# Extern_Kernal_REX9628.net
KiCad netlist of a schematic drawn in EAGLE
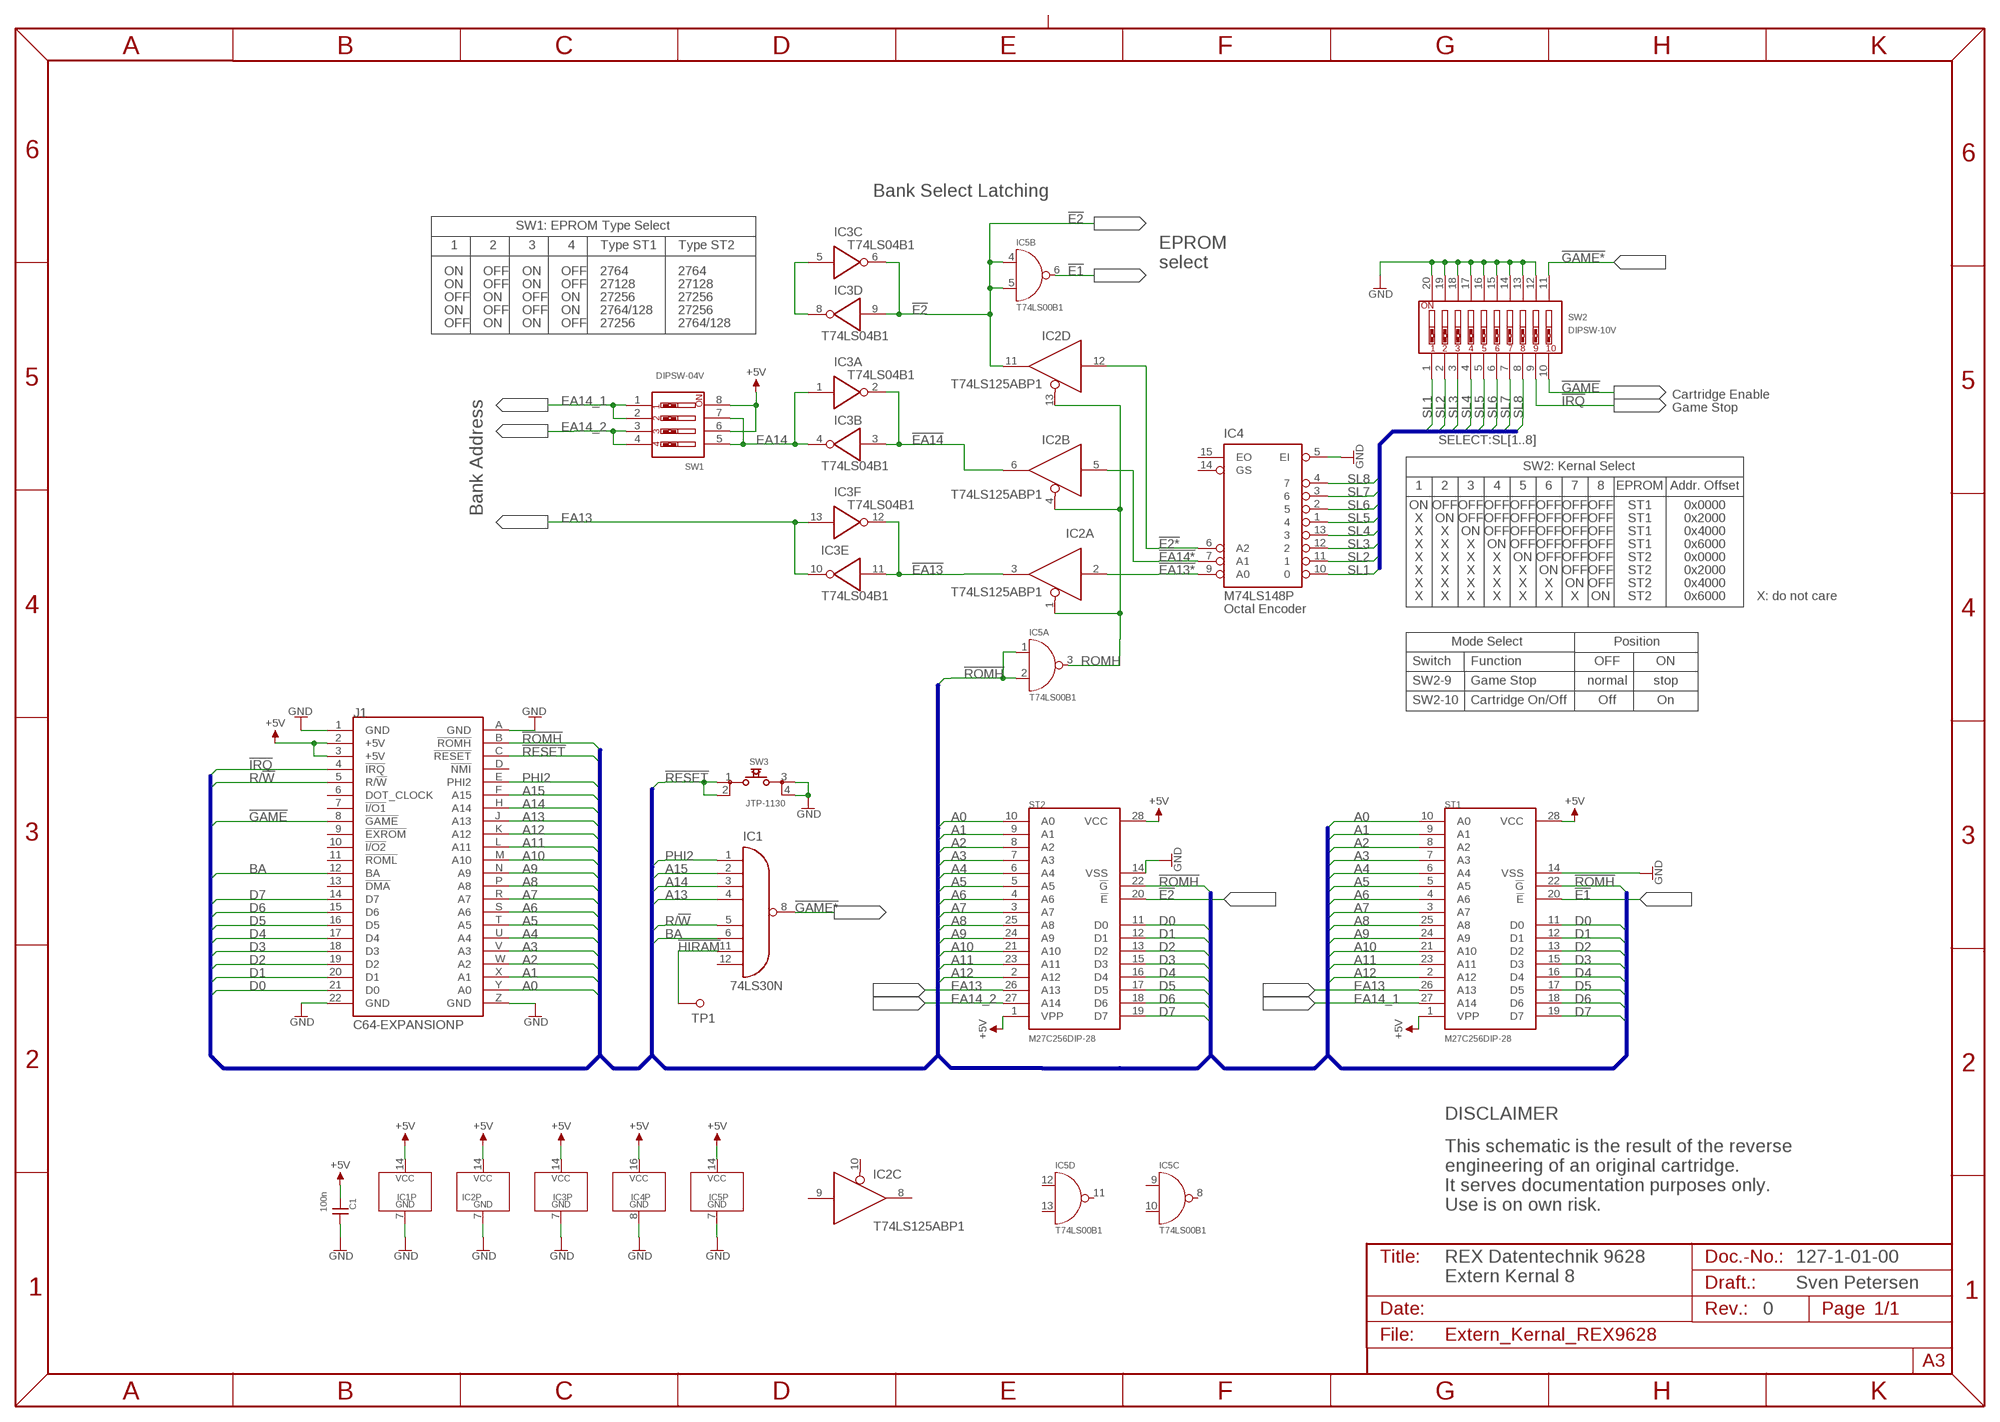
[diagram p0: schematic, sheet 1]

(export (version "E")
  (design (tool "Eeschema 10.0.6"))
  (components
    (comp (ref "C1")
      (value "100n")
      (footprint "eagle-import:C-2,5")
      (libsource (lib "eagle-import") (part "CAP01"))
    )
    (comp (ref "IC1")
      (value "74LS30N")
      (footprint "eagle-import:DIL-14")
      (libsource (lib "eagle-import") (part "7430DIP"))
    )
    (comp (ref "IC2")
      (value "T74LS125ABP1")
      (footprint "eagle-import:DIL-14")
      (libsource (lib "eagle-import") (part "74125DIP"))
    )
    (comp (ref "IC3")
      (value "T74LS04B1")
      (footprint "eagle-import:DIL-14")
      (libsource (lib "eagle-import") (part "7404DIL"))
    )
    (comp (ref "IC4")
      (value "M74LS148P")
      (footprint "eagle-import:DIL-16")
      (libsource (lib "eagle-import") (part "74148DIL"))
    )
    (comp (ref "IC5")
      (value "T74LS00B1")
      (footprint "eagle-import:DIL-14")
      (libsource (lib "eagle-import") (part "7400DIP"))
    )
    (comp (ref "J1")
      (value "C64-EXPANSIONP")
      (footprint "eagle-import:EXPPORT")
      (libsource (lib "eagle-import") (part "C64-EXPANSIONP"))
    )
    (comp (ref "ST1")
      (value "M27C256DIP-28")
      (footprint "eagle-import:DIL28-6")
      (libsource (lib "eagle-import") (part "M27C256DIP-28"))
    )
    (comp (ref "ST2")
      (value "M27C256DIP-28")
      (footprint "eagle-import:DIL28-6")
      (libsource (lib "eagle-import") (part "M27C256DIP-28"))
    )
    (comp (ref "SW1")
      (value "DIPSW-04V")
      (footprint "eagle-import:DIPSW-04V")
      (libsource (lib "eagle-import") (part "DIPSW-04V"))
    )
    (comp (ref "SW2")
      (value "DIPSW-10V")
      (footprint "eagle-import:DIPSW-10V")
      (libsource (lib "eagle-import") (part "DIPSW-10V"))
    )
    (comp (ref "SW3")
      (value "JTP-1130")
      (footprint "eagle-import:JTP-1130")
      (libsource (lib "eagle-import") (part "JTP-1130"))
    )
    (comp (ref "TP1")
      (value "1,3/2,0")
      (footprint "eagle-import:1,3_2,0")
      (libsource (lib "eagle-import") (part "1,3/2,0"))
    )
  )
  (nets
    (net (code "9") (name "+5V") (class "Default")
      (node (ref "C1") (pin "1") (pinfunction "1_1") (pintype "passive"))
      (node (ref "IC1") (pin "14") (pinfunction "VCC_14") (pintype "bidirectional"))
      (node (ref "IC2") (pin "14") (pinfunction "VCC_14") (pintype "bidirectional"))
      (node (ref "IC3") (pin "14") (pinfunction "VCC_14") (pintype "bidirectional"))
      (node (ref "IC4") (pin "16") (pinfunction "VCC_16") (pintype "bidirectional"))
      (node (ref "IC5") (pin "14") (pinfunction "VCC_14") (pintype "bidirectional"))
      (node (ref "J1") (pin "2") (pinfunction "+5V_2") (pintype "power_in"))
      (node (ref "J1") (pin "3") (pinfunction "+5V_3") (pintype "power_in"))
      (node (ref "ST1") (pin "1") (pinfunction "VPP_1") (pintype "input"))
      (node (ref "ST1") (pin "28") (pinfunction "VCC_28") (pintype "power_in"))
      (node (ref "ST2") (pin "1") (pinfunction "VPP_1") (pintype "input"))
      (node (ref "ST2") (pin "28") (pinfunction "VCC_28") (pintype "power_in"))
      (node (ref "SW1") (pin "6") (pinfunction "6_6") (pintype "passive"))
      (node (ref "SW1") (pin "8") (pinfunction "8_8") (pintype "passive"))
    )
    (net (code "10") (name "/A0") (class "Default")
      (node (ref "J1") (pin "Y") (pinfunction "A0_Y") (pintype "bidirectional"))
      (node (ref "ST1") (pin "10") (pinfunction "A0_10") (pintype "input"))
      (node (ref "ST2") (pin "10") (pinfunction "A0_10") (pintype "input"))
    )
    (net (code "11") (name "/A1") (class "Default")
      (node (ref "J1") (pin "X") (pinfunction "A1_X") (pintype "bidirectional"))
      (node (ref "ST1") (pin "9") (pinfunction "A1_9") (pintype "input"))
      (node (ref "ST2") (pin "9") (pinfunction "A1_9") (pintype "input"))
    )
    (net (code "12") (name "/A2") (class "Default")
      (node (ref "J1") (pin "W") (pinfunction "A2_W") (pintype "bidirectional"))
      (node (ref "ST1") (pin "8") (pinfunction "A2_8") (pintype "input"))
      (node (ref "ST2") (pin "8") (pinfunction "A2_8") (pintype "input"))
    )
    (net (code "13") (name "/A3") (class "Default")
      (node (ref "J1") (pin "V") (pinfunction "A3_V") (pintype "bidirectional"))
      (node (ref "ST1") (pin "7") (pinfunction "A3_7") (pintype "input"))
      (node (ref "ST2") (pin "7") (pinfunction "A3_7") (pintype "input"))
    )
    (net (code "14") (name "/A4") (class "Default")
      (node (ref "J1") (pin "U") (pinfunction "A4_U") (pintype "bidirectional"))
      (node (ref "ST1") (pin "6") (pinfunction "A4_6") (pintype "input"))
      (node (ref "ST2") (pin "6") (pinfunction "A4_6") (pintype "input"))
    )
    (net (code "15") (name "/A5") (class "Default")
      (node (ref "J1") (pin "T") (pinfunction "A5_T") (pintype "bidirectional"))
      (node (ref "ST1") (pin "5") (pinfunction "A5_5") (pintype "input"))
      (node (ref "ST2") (pin "5") (pinfunction "A5_5") (pintype "input"))
    )
    (net (code "16") (name "/A6") (class "Default")
      (node (ref "J1") (pin "S") (pinfunction "A6_S") (pintype "bidirectional"))
      (node (ref "ST1") (pin "4") (pinfunction "A6_4") (pintype "input"))
      (node (ref "ST2") (pin "4") (pinfunction "A6_4") (pintype "input"))
    )
    (net (code "17") (name "/A7") (class "Default")
      (node (ref "J1") (pin "R") (pinfunction "A7_R") (pintype "bidirectional"))
      (node (ref "ST1") (pin "3") (pinfunction "A7_3") (pintype "input"))
      (node (ref "ST2") (pin "3") (pinfunction "A7_3") (pintype "input"))
    )
    (net (code "18") (name "/A8") (class "Default")
      (node (ref "J1") (pin "P") (pinfunction "A8_P") (pintype "bidirectional"))
      (node (ref "ST1") (pin "25") (pinfunction "A8_25") (pintype "input"))
      (node (ref "ST2") (pin "25") (pinfunction "A8_25") (pintype "input"))
    )
    (net (code "19") (name "/A9") (class "Default")
      (node (ref "J1") (pin "N") (pinfunction "A9_N") (pintype "bidirectional"))
      (node (ref "ST1") (pin "24") (pinfunction "A9_24") (pintype "input"))
      (node (ref "ST2") (pin "24") (pinfunction "A9_24") (pintype "input"))
    )
    (net (code "20") (name "/A10") (class "Default")
      (node (ref "J1") (pin "M") (pinfunction "A10_M") (pintype "bidirectional"))
      (node (ref "ST1") (pin "21") (pinfunction "A10_21") (pintype "input"))
      (node (ref "ST2") (pin "21") (pinfunction "A10_21") (pintype "input"))
    )
    (net (code "21") (name "/A11") (class "Default")
      (node (ref "J1") (pin "L") (pinfunction "A11_L") (pintype "bidirectional"))
      (node (ref "ST1") (pin "23") (pinfunction "A11_23") (pintype "input"))
      (node (ref "ST2") (pin "23") (pinfunction "A11_23") (pintype "input"))
    )
    (net (code "22") (name "/A12") (class "Default")
      (node (ref "J1") (pin "K") (pinfunction "A12_K") (pintype "bidirectional"))
      (node (ref "ST1") (pin "2") (pinfunction "A12_2") (pintype "input"))
      (node (ref "ST2") (pin "2") (pinfunction "A12_2") (pintype "input"))
    )
    (net (code "23") (name "/A13") (class "Default")
      (node (ref "IC1") (pin "4") (pinfunction "I3_4") (pintype "input"))
      (node (ref "J1") (pin "J") (pinfunction "A13_J") (pintype "bidirectional"))
    )
    (net (code "24") (name "/A14") (class "Default")
      (node (ref "IC1") (pin "3") (pinfunction "I2_3") (pintype "input"))
      (node (ref "J1") (pin "H") (pinfunction "A14_H") (pintype "bidirectional"))
    )
    (net (code "25") (name "/A15") (class "Default")
      (node (ref "IC1") (pin "2") (pinfunction "I1_2") (pintype "input"))
      (node (ref "J1") (pin "F") (pinfunction "A15_F") (pintype "bidirectional"))
    )
    (net (code "26") (name "/BA") (class "Default")
      (node (ref "IC1") (pin "6") (pinfunction "I5_6") (pintype "input"))
      (node (ref "J1") (pin "12") (pinfunction "BA_12") (pintype "output"))
    )
    (net (code "27") (name "/D0") (class "Default")
      (node (ref "J1") (pin "21") (pinfunction "D0_21") (pintype "bidirectional"))
      (node (ref "ST1") (pin "11") (pinfunction "D0_11") (pintype "bidirectional"))
      (node (ref "ST2") (pin "11") (pinfunction "D0_11") (pintype "bidirectional"))
    )
    (net (code "28") (name "/D1") (class "Default")
      (node (ref "J1") (pin "20") (pinfunction "D1_20") (pintype "bidirectional"))
      (node (ref "ST1") (pin "12") (pinfunction "D1_12") (pintype "bidirectional"))
      (node (ref "ST2") (pin "12") (pinfunction "D1_12") (pintype "bidirectional"))
    )
    (net (code "29") (name "/D2") (class "Default")
      (node (ref "J1") (pin "19") (pinfunction "D2_19") (pintype "bidirectional"))
      (node (ref "ST1") (pin "13") (pinfunction "D2_13") (pintype "bidirectional"))
      (node (ref "ST2") (pin "13") (pinfunction "D2_13") (pintype "bidirectional"))
    )
    (net (code "30") (name "/D3") (class "Default")
      (node (ref "J1") (pin "18") (pinfunction "D3_18") (pintype "bidirectional"))
      (node (ref "ST1") (pin "15") (pinfunction "D3_15") (pintype "bidirectional"))
      (node (ref "ST2") (pin "15") (pinfunction "D3_15") (pintype "bidirectional"))
    )
    (net (code "31") (name "/D4") (class "Default")
      (node (ref "J1") (pin "17") (pinfunction "D4_17") (pintype "bidirectional"))
      (node (ref "ST1") (pin "16") (pinfunction "D4_16") (pintype "bidirectional"))
      (node (ref "ST2") (pin "16") (pinfunction "D4_16") (pintype "bidirectional"))
    )
    (net (code "32") (name "/D5") (class "Default")
      (node (ref "J1") (pin "16") (pinfunction "D5_16") (pintype "bidirectional"))
      (node (ref "ST1") (pin "17") (pinfunction "D5_17") (pintype "bidirectional"))
      (node (ref "ST2") (pin "17") (pinfunction "D5_17") (pintype "bidirectional"))
    )
    (net (code "33") (name "/D6") (class "Default")
      (node (ref "J1") (pin "15") (pinfunction "D6_15") (pintype "bidirectional"))
      (node (ref "ST1") (pin "18") (pinfunction "D6_18") (pintype "bidirectional"))
      (node (ref "ST2") (pin "18") (pinfunction "D6_18") (pintype "bidirectional"))
    )
    (net (code "34") (name "/D7") (class "Default")
      (node (ref "J1") (pin "14") (pinfunction "D7_14") (pintype "bidirectional"))
      (node (ref "ST1") (pin "19") (pinfunction "D7_19") (pintype "bidirectional"))
      (node (ref "ST2") (pin "19") (pinfunction "D7_19") (pintype "bidirectional"))
    )
    (net (code "35") (name "/EA13") (class "Default")
      (node (ref "IC3") (pin "10") (pinfunction "O_10") (pintype "output"))
      (node (ref "IC3") (pin "13") (pinfunction "I_13") (pintype "input"))
      (node (ref "ST1") (pin "26") (pinfunction "A13_26") (pintype "input"))
      (node (ref "ST2") (pin "26") (pinfunction "A13_26") (pintype "input"))
    )
    (net (code "36") (name "/EA14") (class "Default")
      (node (ref "IC3") (pin "1") (pinfunction "I_1") (pintype "input"))
      (node (ref "IC3") (pin "4") (pinfunction "O_4") (pintype "output"))
      (node (ref "SW1") (pin "5") (pinfunction "5_5") (pintype "passive"))
      (node (ref "SW1") (pin "7") (pinfunction "7_7") (pintype "passive"))
    )
    (net (code "37") (name "/EA14_1") (class "Default")
      (node (ref "ST1") (pin "27") (pinfunction "A14_27") (pintype "input"))
      (node (ref "SW1") (pin "1") (pinfunction "1_1") (pintype "passive"))
      (node (ref "SW1") (pin "2") (pinfunction "2_2") (pintype "passive"))
    )
    (net (code "38") (name "/EA14_2") (class "Default")
      (node (ref "ST2") (pin "27") (pinfunction "A14_27") (pintype "input"))
      (node (ref "SW1") (pin "3") (pinfunction "3_3") (pintype "passive"))
      (node (ref "SW1") (pin "4") (pinfunction "4_4") (pintype "passive"))
    )
    (net (code "39") (name "/PHI2") (class "Default")
      (node (ref "IC1") (pin "1") (pinfunction "I0_1") (pintype "input"))
      (node (ref "J1") (pin "E") (pinfunction "PHI2_E") (pintype "output"))
    )
    (net (code "40") (name "/ROMH") (class "Default")
      (node (ref "IC2") (pin "1") (pinfunction "OE_1") (pintype "input"))
      (node (ref "IC2") (pin "13") (pinfunction "OE_13") (pintype "input"))
      (node (ref "IC2") (pin "4") (pinfunction "OE_4") (pintype "input"))
      (node (ref "IC5") (pin "3") (pinfunction "O_3") (pintype "output"))
    )
    (net (code "41") (name "/R{slash}~{W}") (class "Default")
      (node (ref "IC1") (pin "5") (pinfunction "I4_5") (pintype "input"))
      (node (ref "J1") (pin "5") (pinfunction "R/~{W}_5") (pintype "output"))
    )
    (net (code "43") (name "/SL1") (class "Default")
      (node (ref "IC4") (pin "10") (pinfunction "0_10") (pintype "input"))
      (node (ref "SW2") (pin "1") (pinfunction "1_1") (pintype "passive"))
    )
    (net (code "44") (name "/SL2") (class "Default")
      (node (ref "IC4") (pin "11") (pinfunction "1_11") (pintype "input"))
      (node (ref "SW2") (pin "2") (pinfunction "2_2") (pintype "passive"))
    )
    (net (code "45") (name "/SL3") (class "Default")
      (node (ref "IC4") (pin "12") (pinfunction "2_12") (pintype "input"))
      (node (ref "SW2") (pin "3") (pinfunction "3_3") (pintype "passive"))
    )
    (net (code "46") (name "/SL4") (class "Default")
      (node (ref "IC4") (pin "13") (pinfunction "3_13") (pintype "input"))
      (node (ref "SW2") (pin "4") (pinfunction "4_4") (pintype "passive"))
    )
    (net (code "47") (name "/SL5") (class "Default")
      (node (ref "IC4") (pin "1") (pinfunction "4_1") (pintype "input"))
      (node (ref "SW2") (pin "5") (pinfunction "5_5") (pintype "passive"))
    )
    (net (code "48") (name "/SL6") (class "Default")
      (node (ref "IC4") (pin "2") (pinfunction "5_2") (pintype "input"))
      (node (ref "SW2") (pin "6") (pinfunction "6_6") (pintype "passive"))
    )
    (net (code "49") (name "/SL7") (class "Default")
      (node (ref "IC4") (pin "3") (pinfunction "6_3") (pintype "input"))
      (node (ref "SW2") (pin "7") (pinfunction "7_7") (pintype "passive"))
    )
    (net (code "50") (name "/SL8") (class "Default")
      (node (ref "IC4") (pin "4") (pinfunction "7_4") (pintype "input"))
      (node (ref "SW2") (pin "8") (pinfunction "8_8") (pintype "passive"))
    )
    (net (code "51") (name "/~{E1}") (class "Default")
      (node (ref "IC5") (pin "6") (pinfunction "O_6") (pintype "output"))
      (node (ref "ST1") (pin "20") (pinfunction "~{E}_20") (pintype "input"))
    )
    (net (code "52") (name "/~{E2*}") (class "Default")
      (node (ref "IC2") (pin "12") (pinfunction "I_12") (pintype "input"))
      (node (ref "IC4") (pin "6") (pinfunction "A2_6") (pintype "output"))
    )
    (net (code "53") (name "/~{E2}") (class "Default")
      (node (ref "IC2") (pin "11") (pinfunction "O_11") (pintype "tri_state"))
      (node (ref "IC3") (pin "6") (pinfunction "O_6") (pintype "output"))
      (node (ref "IC3") (pin "9") (pinfunction "I_9") (pintype "input"))
      (node (ref "IC5") (pin "4") (pinfunction "I0_4") (pintype "input"))
      (node (ref "IC5") (pin "5") (pinfunction "I1_5") (pintype "input"))
      (node (ref "ST2") (pin "20") (pinfunction "~{E}_20") (pintype "input"))
    )
    (net (code "54") (name "/~{EA13*}") (class "Default")
      (node (ref "IC2") (pin "2") (pinfunction "I_2") (pintype "input"))
      (node (ref "IC4") (pin "9") (pinfunction "A0_9") (pintype "output"))
    )
    (net (code "55") (name "/~{EA13}") (class "Default")
      (node (ref "IC2") (pin "3") (pinfunction "O_3") (pintype "tri_state"))
      (node (ref "IC3") (pin "11") (pinfunction "I_11") (pintype "input"))
      (node (ref "IC3") (pin "12") (pinfunction "O_12") (pintype "output"))
    )
    (net (code "56") (name "/~{EA14*}") (class "Default")
      (node (ref "IC2") (pin "5") (pinfunction "I_5") (pintype "input"))
      (node (ref "IC4") (pin "7") (pinfunction "A1_7") (pintype "output"))
    )
    (net (code "57") (name "/~{EA14}") (class "Default")
      (node (ref "IC2") (pin "6") (pinfunction "O_6") (pintype "tri_state"))
      (node (ref "IC3") (pin "2") (pinfunction "O_2") (pintype "output"))
      (node (ref "IC3") (pin "3") (pinfunction "I_3") (pintype "input"))
    )
    (net (code "58") (name "/~{GAME*}") (class "Default")
      (node (ref "IC1") (pin "8") (pinfunction "O_8") (pintype "output"))
      (node (ref "SW2") (pin "11") (pinfunction "11_11") (pintype "passive"))
    )
    (net (code "59") (name "/~{GAME}") (class "Default")
      (node (ref "J1") (pin "8") (pinfunction "~{GAME}_8") (pintype "input"))
      (node (ref "SW2") (pin "10") (pinfunction "10_10") (pintype "passive"))
    )
    (net (code "60") (name "/~{HIRAM}") (class "Default")
      (node (ref "IC1") (pin "11") (pinfunction "I6_11") (pintype "input"))
      (node (ref "TP1") (pin "1") (pinfunction "1_1") (pintype "passive"))
    )
    (net (code "61") (name "/~{IRQ}") (class "Default")
      (node (ref "J1") (pin "4") (pinfunction "~{IRQ}_4") (pintype "input"))
      (node (ref "SW2") (pin "9") (pinfunction "9_9") (pintype "passive"))
    )
    (net (code "62") (name "/~{RESET}") (class "Default")
      (node (ref "J1") (pin "C") (pinfunction "~{RESET}_C") (pintype "open_collector"))
      (node (ref "SW3") (pin "1") (pinfunction "1_1") (pintype "passive"))
      (node (ref "SW3") (pin "2") (pinfunction "2_2") (pintype "passive"))
    )
    (net (code "63") (name "/~{ROMH}") (class "Default")
      (node (ref "IC5") (pin "1") (pinfunction "I0_1") (pintype "input"))
      (node (ref "IC5") (pin "2") (pinfunction "I1_2") (pintype "input"))
      (node (ref "J1") (pin "B") (pinfunction "~{ROMH}_B") (pintype "output"))
      (node (ref "ST1") (pin "22") (pinfunction "~{G}_22") (pintype "input"))
      (node (ref "ST2") (pin "22") (pinfunction "~{G}_22") (pintype "input"))
    )
    (net (code "64") (name "GND") (class "Default")
      (node (ref "C1") (pin "2") (pinfunction "2_2") (pintype "passive"))
      (node (ref "IC1") (pin "7") (pinfunction "GND_7") (pintype "bidirectional"))
      (node (ref "IC2") (pin "7") (pinfunction "GND_7") (pintype "bidirectional"))
      (node (ref "IC3") (pin "7") (pinfunction "GND_7") (pintype "bidirectional"))
      (node (ref "IC4") (pin "5") (pinfunction "EI_5") (pintype "input"))
      (node (ref "IC4") (pin "8") (pinfunction "GND_8") (pintype "bidirectional"))
      (node (ref "IC5") (pin "7") (pinfunction "GND_7") (pintype "bidirectional"))
      (node (ref "J1") (pin "1") (pinfunction "GND_1") (pintype "power_in"))
      (node (ref "J1") (pin "22") (pinfunction "GND_22") (pintype "power_in"))
      (node (ref "J1") (pin "A") (pinfunction "GND_A") (pintype "power_in"))
      (node (ref "J1") (pin "Z") (pinfunction "GND_Z") (pintype "power_in"))
      (node (ref "ST1") (pin "14") (pinfunction "VSS_14") (pintype "power_in"))
      (node (ref "ST2") (pin "14") (pinfunction "VSS_14") (pintype "power_in"))
      (node (ref "SW2") (pin "12") (pinfunction "12_12") (pintype "passive"))
      (node (ref "SW2") (pin "13") (pinfunction "13_13") (pintype "passive"))
      (node (ref "SW2") (pin "14") (pinfunction "14_14") (pintype "passive"))
      (node (ref "SW2") (pin "15") (pinfunction "15_15") (pintype "passive"))
      (node (ref "SW2") (pin "16") (pinfunction "16_16") (pintype "passive"))
      (node (ref "SW2") (pin "17") (pinfunction "17_17") (pintype "passive"))
      (node (ref "SW2") (pin "18") (pinfunction "18_18") (pintype "passive"))
      (node (ref "SW2") (pin "19") (pinfunction "19_19") (pintype "passive"))
      (node (ref "SW2") (pin "20") (pinfunction "20_20") (pintype "passive"))
      (node (ref "SW3") (pin "3") (pinfunction "3_3") (pintype "passive"))
      (node (ref "SW3") (pin "4") (pinfunction "4_4") (pintype "passive"))
    )
    (net (code "65") (name "Net-(IC3C-I)") (class "Default")
      (node (ref "IC3") (pin "5") (pinfunction "I_5") (pintype "input"))
      (node (ref "IC3") (pin "8") (pinfunction "O_8") (pintype "output"))
    )
    (net (code "66") (name "unconnected-(IC1A-I7-Pad12)") (class "Default")
      (node (ref "IC1") (pin "12") (pinfunction "I7_12") (pintype "input"))
    )
    (net (code "67") (name "unconnected-(IC2C-I-Pad9)") (class "Default")
      (node (ref "IC2") (pin "9") (pinfunction "I_9") (pintype "input"))
    )
    (net (code "68") (name "unconnected-(IC2C-O-Pad8)") (class "Default")
      (node (ref "IC2") (pin "8") (pinfunction "O_8") (pintype "tri_state"))
    )
    (net (code "69") (name "unconnected-(IC2C-OE-Pad10)") (class "Default")
      (node (ref "IC2") (pin "10") (pinfunction "OE_10") (pintype "input"))
    )
    (net (code "70") (name "unconnected-(IC4A-EO-Pad15)") (class "Default")
      (node (ref "IC4") (pin "15") (pinfunction "EO_15") (pintype "output"))
    )
    (net (code "71") (name "unconnected-(IC4A-GS-Pad14)") (class "Default")
      (node (ref "IC4") (pin "14") (pinfunction "GS_14") (pintype "output"))
    )
    (net (code "72") (name "unconnected-(IC5C-I0-Pad9)") (class "Default")
      (node (ref "IC5") (pin "9") (pinfunction "I0_9") (pintype "input"))
    )
    (net (code "73") (name "unconnected-(IC5C-I1-Pad10)") (class "Default")
      (node (ref "IC5") (pin "10") (pinfunction "I1_10") (pintype "input"))
    )
    (net (code "74") (name "unconnected-(IC5C-O-Pad8)") (class "Default")
      (node (ref "IC5") (pin "8") (pinfunction "O_8") (pintype "output"))
    )
    (net (code "75") (name "unconnected-(IC5D-I0-Pad12)") (class "Default")
      (node (ref "IC5") (pin "12") (pinfunction "I0_12") (pintype "input"))
    )
    (net (code "76") (name "unconnected-(IC5D-I1-Pad13)") (class "Default")
      (node (ref "IC5") (pin "13") (pinfunction "I1_13") (pintype "input"))
    )
    (net (code "77") (name "unconnected-(IC5D-O-Pad11)") (class "Default")
      (node (ref "IC5") (pin "11") (pinfunction "O_11") (pintype "output"))
    )
    (net (code "78") (name "unconnected-(J1-DOT_CLOCK-Pad6)") (class "Default")
      (node (ref "J1") (pin "6") (pinfunction "DOT_CLOCK_6") (pintype "output"))
    )
    (net (code "79") (name "unconnected-(J1-~{DMA}-Pad13)") (class "Default")
      (node (ref "J1") (pin "13") (pinfunction "~{DMA}_13") (pintype "input"))
    )
    (net (code "80") (name "unconnected-(J1-~{EXROM}-Pad9)") (class "Default")
      (node (ref "J1") (pin "9") (pinfunction "~{EXROM}_9") (pintype "input"))
    )
    (net (code "81") (name "unconnected-(J1-~{I{slash}O1}-Pad7)") (class "Default")
      (node (ref "J1") (pin "7") (pinfunction "~{I/O1}_7") (pintype "output"))
    )
    (net (code "82") (name "unconnected-(J1-~{I{slash}O2}-Pad10)") (class "Default")
      (node (ref "J1") (pin "10") (pinfunction "~{I/O2}_10") (pintype "output"))
    )
    (net (code "83") (name "unconnected-(J1-~{NMI}-PadD)") (class "Default")
      (node (ref "J1") (pin "D") (pinfunction "~{NMI}_D") (pintype "input"))
    )
    (net (code "84") (name "unconnected-(J1-~{ROML}-Pad11)") (class "Default")
      (node (ref "J1") (pin "11") (pinfunction "~{ROML}_11") (pintype "output"))
    )
  )
)
